# DAC.net
KiCad netlist of a schematic drawn in Altium Designer
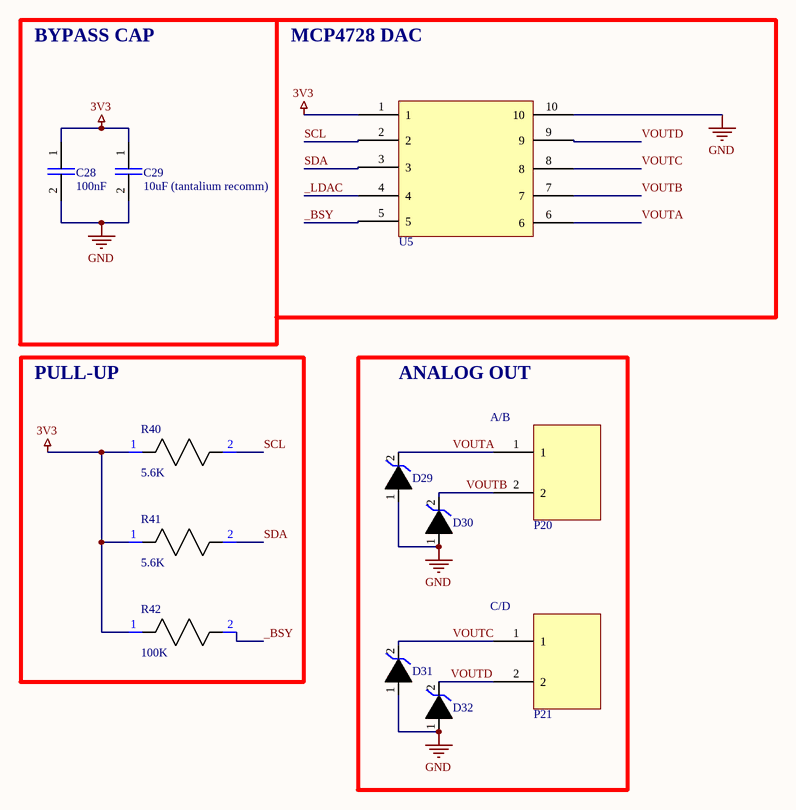
[diagram p0: DAC.SchDoc]

(export (version "E")
  (design (tool "Eeschema 10.0.6"))
  (components
    (comp (ref "C28")
      (value "100nF")
      (footprint "0603 Cap")
      (description "SMD 0603 (ceramic) capacitor")
      (fields
        (field (name "MANUFACTURER") "Murata")
        (field (name "MANUFACTURER PART NUMBER") "GRM21BR71C225KA12L")
      )
      (libsource (lib "Lib") (part "0603 Cap"))
    )
    (comp (ref "C29")
      (value "10uF (tantalium recomm)")
      (footprint "0603 Cap")
      (description "SMD 0603 (ceramic) capacitor")
      (fields
        (field (name "MANUFACTURER") "Murata")
        (field (name "MANUFACTURER PART NUMBER") "GRM21BR71C225KA12L")
      )
      (libsource (lib "Lib") (part "0603 Cap"))
    )
    (comp (ref "D29")
      (value "TVS")
      (footprint "0805 TVS DIODE")
      (description "Schematic for TVS diode")
      (libsource (lib "Lib") (part "TVS Diode"))
    )
    (comp (ref "D30")
      (value "TVS")
      (footprint "0805 TVS DIODE")
      (description "Schematic for TVS diode")
      (libsource (lib "Lib") (part "TVS Diode"))
    )
    (comp (ref "D31")
      (value "TVS")
      (footprint "0805 TVS DIODE")
      (description "Schematic for TVS diode")
      (libsource (lib "Lib") (part "TVS Diode"))
    )
    (comp (ref "D32")
      (value "TVS")
      (footprint "0805 TVS DIODE")
      (description "Schematic for TVS diode")
      (libsource (lib "Lib") (part "TVS Diode"))
    )
    (comp (ref "P20")
      (value "A/B")
      (footprint "WR-TBL 322 2H")
      (description "322 series 2 pin header")
      (libsource (lib "Lib") (part "322-2H"))
    )
    (comp (ref "P21")
      (value "C/D")
      (footprint "WR-TBL 322 2H")
      (description "322 series 2 pin header")
      (libsource (lib "Lib") (part "322-2H"))
    )
    (comp (ref "R40")
      (value "5.6K")
      (footprint "0603 RES")
      (description "Can be used for SMD resistors")
      (fields (field (name "Comment") "Resistor"))
      (libsource (lib "Lib") (part "0603 Res"))
    )
    (comp (ref "R41")
      (value "5.6K")
      (footprint "0603 RES")
      (description "Can be used for SMD resistors")
      (fields (field (name "Comment") "Resistor"))
      (libsource (lib "Lib") (part "0603 Res"))
    )
    (comp (ref "R42")
      (value "100K")
      (footprint "0603 RES")
      (description "Can be used for SMD resistors")
      (fields (field (name "Comment") "Resistor"))
      (libsource (lib "Lib") (part "0603 Res"))
    )
    (comp (ref "U5") (value "MCP4728") (footprint "10-PIN MSOP") (libsource (lib "Lib") (part "10-PIN MSOP")))
  )
  (nets
    (net (code "1") (name "/SCL") (class "Default")
      (node (ref "R40") (pin "2") (pinfunction "21_2") (pintype "passive"))
      (node (ref "U5") (pin "2") (pinfunction "2_2") (pintype "passive"))
    )
    (net (code "2") (name "/SDA") (class "Default")
      (node (ref "R41") (pin "2") (pinfunction "21_2") (pintype "passive"))
      (node (ref "U5") (pin "3") (pinfunction "3_3") (pintype "passive"))
    )
    (net (code "3") (name "/VOUTA") (class "Default")
      (node (ref "D29") (pin "2") (pinfunction "2_2") (pintype "passive"))
      (node (ref "P20") (pin "1") (pinfunction "1_1") (pintype "passive"))
      (node (ref "U5") (pin "6") (pinfunction "6_6") (pintype "passive"))
    )
    (net (code "4") (name "/VOUTB") (class "Default")
      (node (ref "D30") (pin "2") (pinfunction "2_2") (pintype "passive"))
      (node (ref "P20") (pin "2") (pinfunction "2_2") (pintype "passive"))
      (node (ref "U5") (pin "7") (pinfunction "7_7") (pintype "passive"))
    )
    (net (code "5") (name "/VOUTC") (class "Default")
      (node (ref "D31") (pin "2") (pinfunction "2_2") (pintype "passive"))
      (node (ref "P21") (pin "1") (pinfunction "1_1") (pintype "passive"))
      (node (ref "U5") (pin "8") (pinfunction "8_8") (pintype "passive"))
    )
    (net (code "6") (name "/VOUTD") (class "Default")
      (node (ref "D32") (pin "2") (pinfunction "2_2") (pintype "passive"))
      (node (ref "P21") (pin "2") (pinfunction "2_2") (pintype "passive"))
      (node (ref "U5") (pin "9") (pinfunction "9_9") (pintype "passive"))
    )
    (net (code "7") (name "/_BSY") (class "Default")
      (node (ref "R42") (pin "2") (pinfunction "21_2") (pintype "passive"))
      (node (ref "U5") (pin "5") (pinfunction "5_5") (pintype "passive"))
    )
    (net (code "8") (name "/_LDAC") (class "Default")
      (node (ref "U5") (pin "4") (pinfunction "4_4") (pintype "passive"))
    )
    (net (code "9") (name "3V3") (class "Default")
      (node (ref "C28") (pin "1") (pinfunction "11_1") (pintype "passive"))
      (node (ref "C29") (pin "1") (pinfunction "11_1") (pintype "passive"))
      (node (ref "R40") (pin "1") (pinfunction "22_1") (pintype "passive"))
      (node (ref "R41") (pin "1") (pinfunction "22_1") (pintype "passive"))
      (node (ref "R42") (pin "1") (pinfunction "22_1") (pintype "passive"))
      (node (ref "U5") (pin "1") (pinfunction "1_1") (pintype "passive"))
    )
    (net (code "10") (name "GND") (class "Default")
      (node (ref "C28") (pin "2") (pinfunction "12_2") (pintype "passive"))
      (node (ref "C29") (pin "2") (pinfunction "12_2") (pintype "passive"))
      (node (ref "D29") (pin "1") (pinfunction "1_1") (pintype "passive"))
      (node (ref "D30") (pin "1") (pinfunction "1_1") (pintype "passive"))
      (node (ref "D31") (pin "1") (pinfunction "1_1") (pintype "passive"))
      (node (ref "D32") (pin "1") (pinfunction "1_1") (pintype "passive"))
      (node (ref "U5") (pin "10") (pinfunction "10_10") (pintype "passive"))
    )
  )
)
